# CH32L103F8P6-R0.net
KiCad netlist of a schematic drawn in Altium Designer
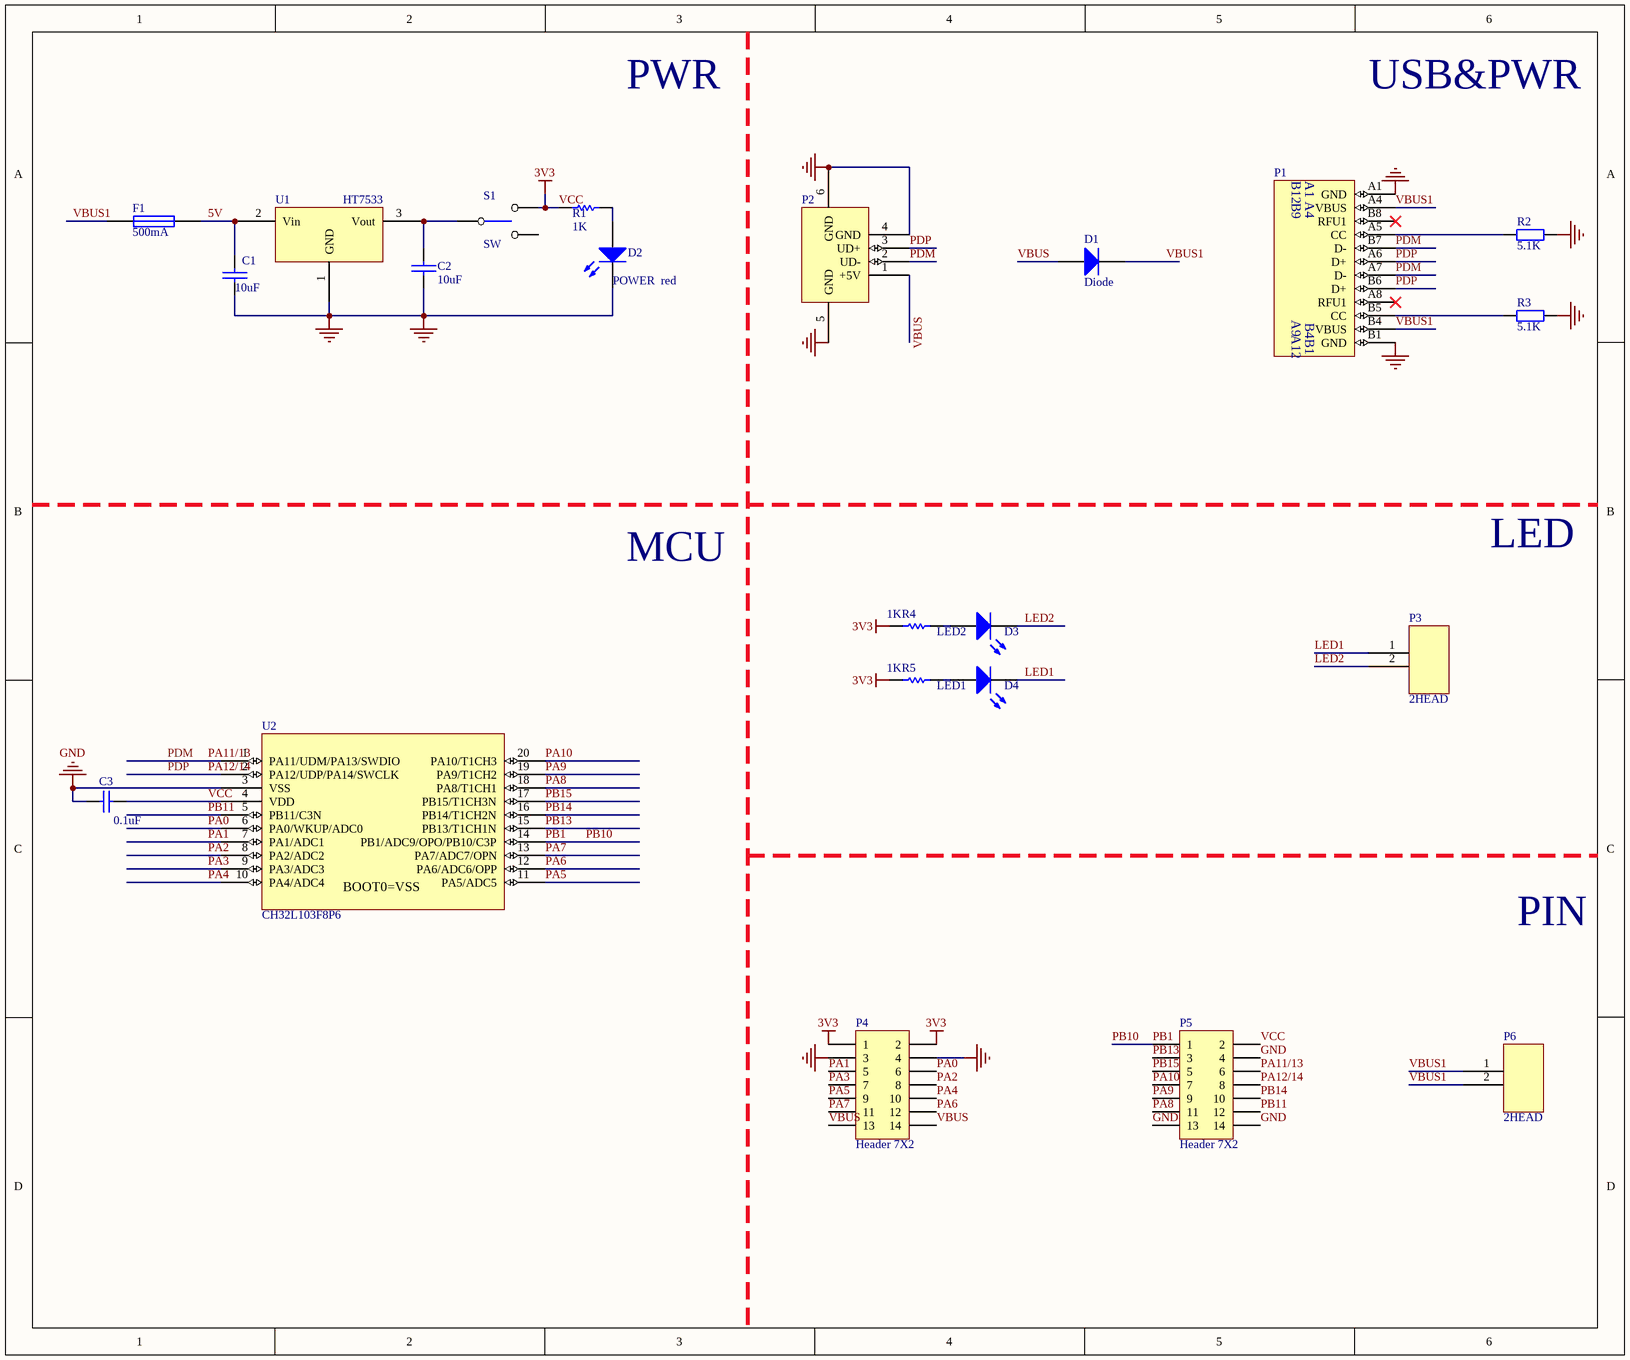
[diagram p0: CH32L103F8P6-R0.SchDoc]

(export (version "E")
  (design (tool "Eeschema 10.0.6"))
  (components
    (comp (ref "C1")
      (value "10uF")
      (footprint "0603_C")
      (description "Capacitor")
      (libsource (lib "*") (part "CAP"))
    )
    (comp (ref "C2")
      (value "10uF")
      (footprint "0603_C")
      (description "Capacitor")
      (libsource (lib "*") (part "CAP"))
    )
    (comp (ref "C3")
      (value "0.1uF")
      (footprint "0603_C")
      (description "Capacitor")
      (fields (field (name "PUBLISHER") "Altium Limited"))
      (libsource (lib "*") (part "Cap"))
    )
    (comp (ref "D1")
      (value "Diode")
      (footprint "SOD-123")
      (description "Default Diode")
      (fields (field (name "PUBLISHER") "Altium Limited"))
      (libsource (lib "Miscellaneous Devices") (part "Diode"))
    )
    (comp (ref "D2")
      (value "POWER  red")
      (footprint "0603+")
      (description "Typical INFRARED GaAs LED")
      (fields (field (name "PUBLISHER") "Altium Limited"))
      (libsource (lib "*") (part "LED0"))
    )
    (comp (ref "D3")
      (value "LED2")
      (footprint "0603+")
      (description "Typical INFRARED GaAs LED")
      (fields (field (name "PUBLISHER") "Altium Limited"))
      (libsource (lib "*") (part "LED0"))
    )
    (comp (ref "D4")
      (value "LED1")
      (footprint "0603+")
      (description "Typical INFRARED GaAs LED")
      (fields (field (name "PUBLISHER") "Altium Limited"))
      (libsource (lib "*") (part "LED0"))
    )
    (comp (ref "F1")
      (value "500mA")
      (footprint "0603")
      (description "Fuse")
      (libsource (lib "*") (part "FUSE1"))
    )
    (comp (ref "P1")
      (value "TYPE-C")
      (footprint "TYPE-C-Receptacle-2.0")
      (libsource (lib "*") (part "TYPE-C1"))
    )
    (comp (ref "P2")
      (value "USB_A")
      (footprint "USBAF")
      (description "USB Port")
      (libsource (lib "*") (part "USB"))
    )
    (comp (ref "P3") (value "2HEAD") (footprint "SIP2-2.54mm") (libsource (lib "*") (part "2HEAD")))
    (comp (ref "P4")
      (value "Header 7X2")
      (footprint "IDC14-2.54mm")
      (description "Header, 7-Pin, Dual row")
      (fields (field (name "PUBLISHER") "Altium Limited"))
      (libsource (lib "Miscellaneous Connectors") (part "Header 7X2"))
    )
    (comp (ref "P5")
      (value "Header 7X2")
      (footprint "IDC14-2.54mm")
      (description "Header, 7-Pin, Dual row")
      (fields (field (name "PUBLISHER") "Altium Limited"))
      (libsource (lib "Miscellaneous Connectors") (part "Header 7X2"))
    )
    (comp (ref "P6") (value "2HEAD") (footprint "SIP2-2.54mm") (libsource (lib "*") (part "2HEAD")))
    (comp (ref "R1")
      (value "1K")
      (footprint "0603")
      (description "Semiconductor Resistor")
      (libsource (lib "*") (part "Res Semi"))
    )
    (comp (ref "R2")
      (value "5.1K")
      (footprint "0603")
      (description "Resistor")
      (libsource (lib "Miscellaneous Devices") (part "Res2"))
    )
    (comp (ref "R3")
      (value "5.1K")
      (footprint "0603")
      (description "Resistor")
      (libsource (lib "Miscellaneous Devices") (part "Res2"))
    )
    (comp (ref "R4")
      (value "1K")
      (footprint "0603")
      (description "Semiconductor Resistor")
      (libsource (lib "*") (part "Res Semi"))
    )
    (comp (ref "R5")
      (value "1K")
      (footprint "0603")
      (description "Semiconductor Resistor")
      (libsource (lib "*") (part "Res Semi"))
    )
    (comp (ref "S1") (value "SW") (footprint "SW1") (libsource (lib "*") (part "SW")))
    (comp (ref "U1")
      (value "HT7533")
      (footprint "SOT-89")
      (libsource (lib "wch_sch_others") (part "1117-3.3V"))
    )
    (comp (ref "U2")
      (value "CH32L103F8P6")
      (footprint "TSSOP20")
      (description "RISC-V LMD-MCU, 96MHz, USB, CAN, OPA, lower power, for motor")
      (libsource (lib "CHXXX") (part "CH32L103F8P6"))
    )
  )
  (nets
    (net (code "1") (name "/5V") (class "Default")
      (node (ref "C1") (pin "1") (pinfunction "1_1") (pintype "passive"))
      (node (ref "F1") (pin "2") (pinfunction "2_2") (pintype "passive"))
      (node (ref "U1") (pin "2") (pinfunction "Vin_2") (pintype "passive"))
    )
    (net (code "3") (name "/LED1") (class "Default")
      (node (ref "D4") (pin "2") (pinfunction "K_2") (pintype "passive"))
      (node (ref "P3") (pin "1") (pintype "passive"))
    )
    (net (code "4") (name "/LED2") (class "Default")
      (node (ref "D3") (pin "2") (pinfunction "K_2") (pintype "passive"))
      (node (ref "P3") (pin "2") (pintype "passive"))
    )
    (net (code "5") (name "/PA0") (class "Default")
      (node (ref "P4") (pin "6") (pinfunction "6_6") (pintype "passive"))
      (node (ref "U2") (pin "6") (pinfunction "PA0/WKUP/ADC0_6") (pintype "bidirectional"))
    )
    (net (code "6") (name "/PA1") (class "Default")
      (node (ref "P4") (pin "5") (pinfunction "5_5") (pintype "passive"))
      (node (ref "U2") (pin "7") (pinfunction "PA1/ADC1_7") (pintype "bidirectional"))
    )
    (net (code "7") (name "/PA2") (class "Default")
      (node (ref "P4") (pin "8") (pinfunction "8_8") (pintype "passive"))
      (node (ref "U2") (pin "8") (pinfunction "PA2/ADC2_8") (pintype "bidirectional"))
    )
    (net (code "8") (name "/PA3") (class "Default")
      (node (ref "P4") (pin "7") (pinfunction "7_7") (pintype "passive"))
      (node (ref "U2") (pin "9") (pinfunction "PA3/ADC3_9") (pintype "bidirectional"))
    )
    (net (code "9") (name "/PA4") (class "Default")
      (node (ref "P4") (pin "10") (pinfunction "10_10") (pintype "passive"))
      (node (ref "U2") (pin "10") (pinfunction "PA4/ADC4_10") (pintype "bidirectional"))
    )
    (net (code "10") (name "/PA5") (class "Default")
      (node (ref "P4") (pin "9") (pinfunction "9_9") (pintype "passive"))
      (node (ref "U2") (pin "11") (pinfunction "PA5/ADC5_11") (pintype "bidirectional"))
    )
    (net (code "11") (name "/PA6") (class "Default")
      (node (ref "P4") (pin "12") (pinfunction "12_12") (pintype "passive"))
      (node (ref "U2") (pin "12") (pinfunction "PA6/ADC6/OPP_12") (pintype "bidirectional"))
    )
    (net (code "12") (name "/PA7") (class "Default")
      (node (ref "P4") (pin "11") (pinfunction "11_11") (pintype "passive"))
      (node (ref "U2") (pin "13") (pinfunction "PA7/ADC7/OPN_13") (pintype "bidirectional"))
    )
    (net (code "13") (name "/PA8") (class "Default")
      (node (ref "P5") (pin "11") (pinfunction "11_11") (pintype "passive"))
      (node (ref "U2") (pin "18") (pinfunction "PA8/T1CH1_18") (pintype "bidirectional"))
    )
    (net (code "14") (name "/PA9") (class "Default")
      (node (ref "P5") (pin "9") (pinfunction "9_9") (pintype "passive"))
      (node (ref "U2") (pin "19") (pinfunction "PA9/T1CH2_19") (pintype "bidirectional"))
    )
    (net (code "15") (name "/PA10") (class "Default")
      (node (ref "P5") (pin "7") (pinfunction "7_7") (pintype "passive"))
      (node (ref "U2") (pin "20") (pinfunction "PA10/T1CH3_20") (pintype "bidirectional"))
    )
    (net (code "16") (name "/PA11{slash}13") (class "Default")
      (node (ref "P1") (pin "A7") (pinfunction "D-_A7") (pintype "bidirectional"))
      (node (ref "P1") (pin "B7") (pinfunction "D-_B7") (pintype "bidirectional"))
      (node (ref "P2") (pin "2") (pinfunction "UD-_2") (pintype "bidirectional"))
      (node (ref "P5") (pin "6") (pinfunction "6_6") (pintype "passive"))
      (node (ref "U2") (pin "1") (pinfunction "PA11/UDM/PA13/SWDIO_1") (pintype "bidirectional"))
    )
    (net (code "17") (name "/PA12{slash}14") (class "Default")
      (node (ref "P1") (pin "A6") (pinfunction "D+_A6") (pintype "bidirectional"))
      (node (ref "P1") (pin "B6") (pinfunction "D+_B6") (pintype "bidirectional"))
      (node (ref "P2") (pin "3") (pinfunction "UD+_3") (pintype "bidirectional"))
      (node (ref "P5") (pin "8") (pinfunction "8_8") (pintype "passive"))
      (node (ref "U2") (pin "2") (pinfunction "PA12/UDP/PA14/SWCLK_2") (pintype "bidirectional"))
    )
    (net (code "18") (name "/PB1") (class "Default")
      (node (ref "P5") (pin "1") (pinfunction "1_1") (pintype "passive"))
      (node (ref "U2") (pin "14") (pinfunction "PB1/ADC9/OPO/PB10/C3P_14") (pintype "bidirectional"))
    )
    (net (code "19") (name "/PB11") (class "Default")
      (node (ref "P5") (pin "12") (pinfunction "12_12") (pintype "passive"))
      (node (ref "U2") (pin "5") (pinfunction "PB11/C3N_5") (pintype "bidirectional"))
    )
    (net (code "20") (name "/PB13") (class "Default")
      (node (ref "P5") (pin "3") (pinfunction "3_3") (pintype "passive"))
      (node (ref "U2") (pin "15") (pinfunction "PB13/T1CH1N_15") (pintype "bidirectional"))
    )
    (net (code "21") (name "/PB14") (class "Default")
      (node (ref "P5") (pin "10") (pinfunction "10_10") (pintype "passive"))
      (node (ref "U2") (pin "16") (pinfunction "PB14/T1CH2N_16") (pintype "bidirectional"))
    )
    (net (code "22") (name "/PB15") (class "Default")
      (node (ref "P5") (pin "5") (pinfunction "5_5") (pintype "passive"))
      (node (ref "U2") (pin "17") (pinfunction "PB15/T1CH3N_17") (pintype "bidirectional"))
    )
    (net (code "23") (name "/VBUS") (class "Default")
      (node (ref "D1") (pin "1") (pinfunction "A_1") (pintype "passive"))
      (node (ref "P2") (pin "1") (pinfunction "+5V_1") (pintype "power_in"))
      (node (ref "P4") (pin "13") (pinfunction "13_13") (pintype "passive"))
      (node (ref "P4") (pin "14") (pinfunction "14_14") (pintype "passive"))
    )
    (net (code "24") (name "/VBUS1") (class "Default")
      (node (ref "D1") (pin "2") (pinfunction "K_2") (pintype "passive"))
      (node (ref "F1") (pin "1") (pinfunction "1_1") (pintype "passive"))
      (node (ref "P1") (pin "A4") (pinfunction "VBUS_A4") (pintype "bidirectional"))
      (node (ref "P1") (pin "B4") (pinfunction "VBUS_B4") (pintype "bidirectional"))
      (node (ref "P6") (pin "1") (pintype "passive"))
      (node (ref "P6") (pin "2") (pintype "passive"))
    )
    (net (code "25") (name "3V3") (class "Default")
      (node (ref "C3") (pin "2") (pinfunction "2_2") (pintype "passive"))
      (node (ref "P4") (pin "1") (pinfunction "1_1") (pintype "passive"))
      (node (ref "P4") (pin "2") (pinfunction "2_2") (pintype "passive"))
      (node (ref "P5") (pin "2") (pinfunction "2_2") (pintype "passive"))
      (node (ref "R1") (pin "2") (pinfunction "2_2") (pintype "passive"))
      (node (ref "R4") (pin "1") (pinfunction "1_1") (pintype "passive"))
      (node (ref "R5") (pin "1") (pinfunction "1_1") (pintype "passive"))
      (node (ref "S1") (pin "3") (pinfunction "3_3") (pintype "passive"))
      (node (ref "U2") (pin "4") (pinfunction "VDD_4") (pintype "power_in"))
    )
    (net (code "26") (name "GND") (class "Default")
      (node (ref "C1") (pin "2") (pinfunction "2_2") (pintype "passive"))
      (node (ref "C2") (pin "2") (pinfunction "2_2") (pintype "passive"))
      (node (ref "C3") (pin "1") (pinfunction "1_1") (pintype "passive"))
      (node (ref "D2") (pin "2") (pinfunction "K_2") (pintype "passive"))
      (node (ref "P1") (pin "A1") (pinfunction "GND_A1") (pintype "bidirectional"))
      (node (ref "P1") (pin "B1") (pinfunction "GND_B1") (pintype "bidirectional"))
      (node (ref "P2") (pin "4") (pinfunction "GND_4") (pintype "power_in"))
      (node (ref "P2") (pin "5") (pinfunction "GND_5") (pintype "power_in"))
      (node (ref "P2") (pin "6") (pinfunction "GND_6") (pintype "power_in"))
      (node (ref "P4") (pin "3") (pinfunction "3_3") (pintype "passive"))
      (node (ref "P4") (pin "4") (pinfunction "4_4") (pintype "passive"))
      (node (ref "P5") (pin "13") (pinfunction "13_13") (pintype "passive"))
      (node (ref "P5") (pin "14") (pinfunction "14_14") (pintype "passive"))
      (node (ref "P5") (pin "4") (pinfunction "4_4") (pintype "passive"))
      (node (ref "R2") (pin "2") (pinfunction "2_2") (pintype "passive"))
      (node (ref "R3") (pin "2") (pinfunction "2_2") (pintype "passive"))
      (node (ref "U1") (pin "1") (pinfunction "GND_1") (pintype "passive"))
      (node (ref "U2") (pin "3") (pinfunction "VSS_3") (pintype "power_in"))
    )
    (net (code "27") (name "Net-(D2-A)") (class "Default")
      (node (ref "D2") (pin "1") (pinfunction "A_1") (pintype "passive"))
      (node (ref "R1") (pin "1") (pinfunction "1_1") (pintype "passive"))
    )
    (net (code "28") (name "Net-(D3-A)") (class "Default")
      (node (ref "D3") (pin "1") (pinfunction "A_1") (pintype "passive"))
      (node (ref "R4") (pin "2") (pinfunction "2_2") (pintype "passive"))
    )
    (net (code "29") (name "Net-(D4-A)") (class "Default")
      (node (ref "D4") (pin "1") (pinfunction "A_1") (pintype "passive"))
      (node (ref "R5") (pin "2") (pinfunction "2_2") (pintype "passive"))
    )
    (net (code "30") (name "Net-(P1-CC-PadA5)") (class "Default")
      (node (ref "P1") (pin "A5") (pinfunction "CC_A5") (pintype "bidirectional"))
      (node (ref "R2") (pin "1") (pinfunction "1_1") (pintype "passive"))
    )
    (net (code "31") (name "Net-(P1-CC-PadB5)") (class "Default")
      (node (ref "P1") (pin "B5") (pinfunction "CC_B5") (pintype "bidirectional"))
      (node (ref "R3") (pin "1") (pinfunction "1_1") (pintype "passive"))
    )
    (net (code "32") (name "Net-(U1-Vout)") (class "Default")
      (node (ref "C2") (pin "1") (pinfunction "1_1") (pintype "passive"))
      (node (ref "S1") (pin "1") (pinfunction "1_1") (pintype "passive"))
      (node (ref "U1") (pin "3") (pinfunction "Vout_3") (pintype "passive"))
    )
    (net (code "33") (name "unconnected-(P1-RFU1-PadA8)") (class "Default")
      (node (ref "P1") (pin "A8") (pinfunction "RFU1_A8") (pintype "bidirectional+no_connect"))
    )
    (net (code "34") (name "unconnected-(P1-RFU1-PadB8)") (class "Default")
      (node (ref "P1") (pin "B8") (pinfunction "RFU1_B8") (pintype "bidirectional+no_connect"))
    )
    (net (code "35") (name "unconnected-(S1-Pad2)") (class "Default")
      (node (ref "S1") (pin "2") (pinfunction "2_2") (pintype "passive"))
    )
  )
)
